# untitled.net
KiCad netlist of a schematic drawn in EAGLE
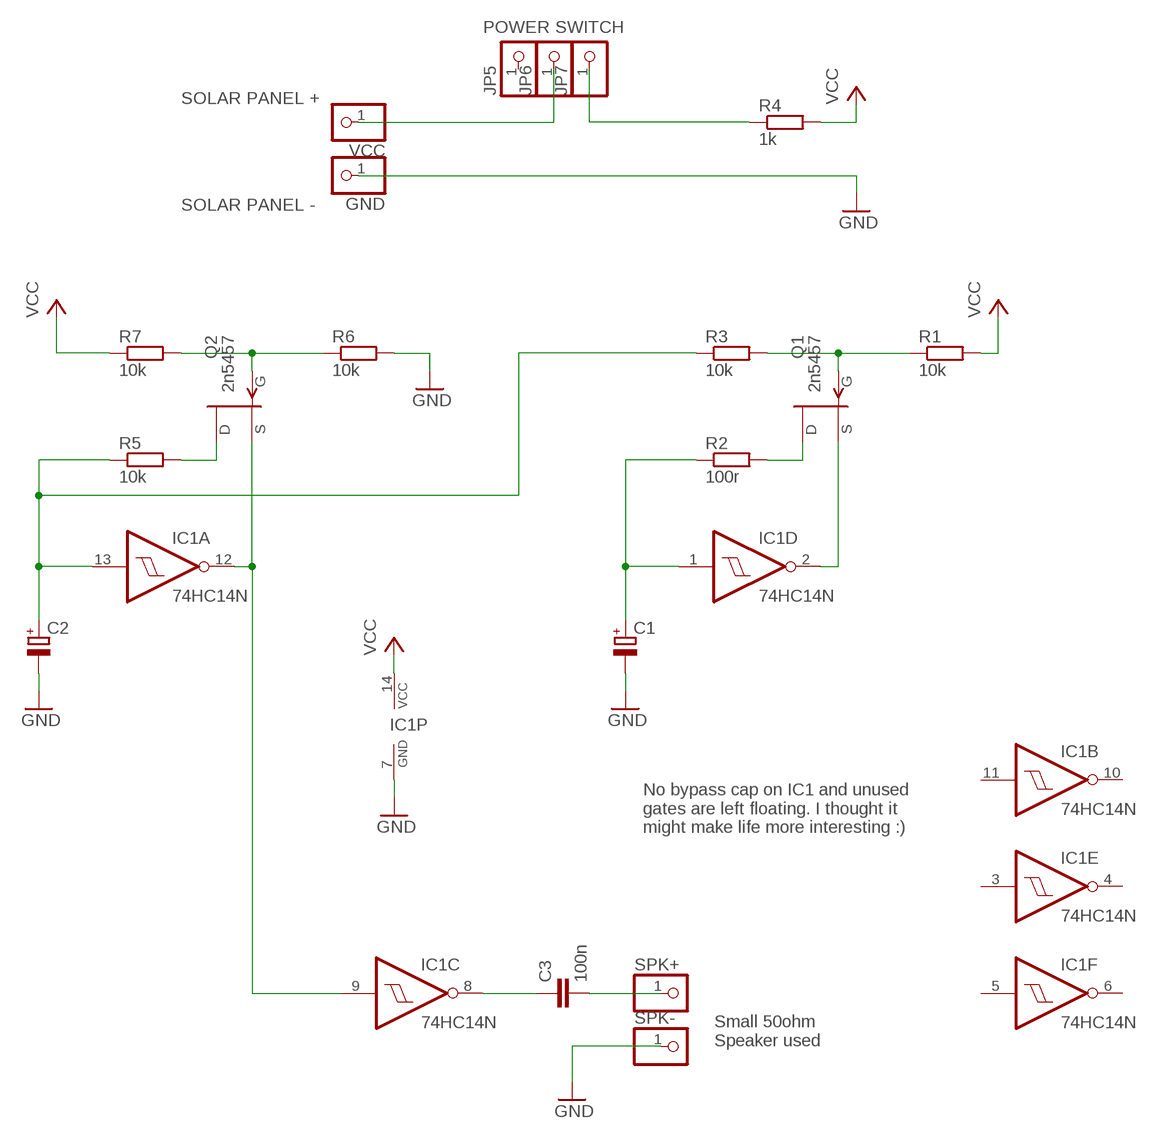
[diagram p0: schematic, sheet 1]

(export (version "E")
  (design (tool "Eeschema 10.0.6"))
  (components
    (comp (ref "C1")
      (value "CPOL-EUE2.5-5")
      (footprint "eagle-import:E2,5-5")
      (libsource (lib "eagle-import") (part "CPOL-EUE2.5-5"))
    )
    (comp (ref "C2")
      (value "CPOL-EUE2.5-5")
      (footprint "eagle-import:E2,5-5")
      (libsource (lib "eagle-import") (part "CPOL-EUE2.5-5"))
    )
    (comp (ref "C3")
      (value "100n")
      (footprint "eagle-import:C025-025X050")
      (libsource (lib "eagle-import") (part "C-EU025-025X050"))
    )
    (comp (ref "GND")
      (value "PINHD-1X1")
      (footprint "eagle-import:1X01")
      (libsource (lib "eagle-import") (part "PINHD-1X1"))
    )
    (comp (ref "IC1")
      (value "74HC14N")
      (footprint "eagle-import:DIL14")
      (libsource (lib "eagle-import") (part "7414NHC"))
    )
    (comp (ref "JP5")
      (value "PINHD-1X1")
      (footprint "eagle-import:1X01")
      (libsource (lib "eagle-import") (part "PINHD-1X1"))
    )
    (comp (ref "JP6")
      (value "PINHD-1X1")
      (footprint "eagle-import:1X01")
      (libsource (lib "eagle-import") (part "PINHD-1X1"))
    )
    (comp (ref "JP7")
      (value "PINHD-1X1")
      (footprint "eagle-import:1X01")
      (libsource (lib "eagle-import") (part "PINHD-1X1"))
    )
    (comp (ref "Q1")
      (value "2n5457")
      (footprint "eagle-import:TO92-")
      (libsource (lib "eagle-import") (part "?5482N4"))
    )
    (comp (ref "Q2")
      (value "2n5457")
      (footprint "eagle-import:TO92-")
      (libsource (lib "eagle-import") (part "?5482N4"))
    )
    (comp (ref "R1")
      (value "10k")
      (footprint "eagle-import:0207_10")
      (libsource (lib "eagle-import") (part "R-EU_0207/10"))
    )
    (comp (ref "R2")
      (value "100r")
      (footprint "eagle-import:0207_10")
      (libsource (lib "eagle-import") (part "R-EU_0207/10"))
    )
    (comp (ref "R3")
      (value "10k")
      (footprint "eagle-import:0207_10")
      (libsource (lib "eagle-import") (part "R-EU_0207/10"))
    )
    (comp (ref "R4")
      (value "1k")
      (footprint "eagle-import:0207_10")
      (libsource (lib "eagle-import") (part "R-EU_0207/10"))
    )
    (comp (ref "R5")
      (value "10k")
      (footprint "eagle-import:0207_10")
      (libsource (lib "eagle-import") (part "R-EU_0207/10"))
    )
    (comp (ref "R6")
      (value "10k")
      (footprint "eagle-import:0207_10")
      (libsource (lib "eagle-import") (part "R-EU_0207/10"))
    )
    (comp (ref "R7")
      (value "10k")
      (footprint "eagle-import:0207_10")
      (libsource (lib "eagle-import") (part "R-EU_0207/10"))
    )
    (comp (ref "SPK+")
      (value "PINHD-1X1")
      (footprint "eagle-import:1X01")
      (libsource (lib "eagle-import") (part "PINHD-1X1"))
    )
    (comp (ref "SPK-")
      (value "PINHD-1X1")
      (footprint "eagle-import:1X01")
      (libsource (lib "eagle-import") (part "PINHD-1X1"))
    )
    (comp (ref "VCC")
      (value "PINHD-1X1")
      (footprint "eagle-import:1X01")
      (libsource (lib "eagle-import") (part "PINHD-1X1"))
    )
  )
  (nets
    (net (code "1") (name "GND") (class "Default")
      (node (ref "C1") (pin "-") (pinfunction "-_-") (pintype "passive"))
      (node (ref "C2") (pin "-") (pinfunction "-_-") (pintype "passive"))
      (node (ref "GND") (pin "1") (pinfunction "1_1") (pintype "passive"))
      (node (ref "IC1") (pin "7") (pinfunction "GND_7") (pintype "power_in"))
      (node (ref "R6") (pin "2") (pinfunction "2_2") (pintype "passive"))
      (node (ref "SPK-") (pin "1") (pinfunction "1_1") (pintype "passive"))
    )
    (net (code "2") (name "Net-(C3-Pad2)") (class "Default")
      (node (ref "C3") (pin "2") (pinfunction "2_2") (pintype "passive"))
      (node (ref "SPK+") (pin "1") (pinfunction "1_1") (pintype "passive"))
    )
    (net (code "3") (name "Net-(IC1A-I)") (class "Default")
      (node (ref "C2") (pin "+") (pinfunction "+_+") (pintype "passive"))
      (node (ref "IC1") (pin "13") (pinfunction "I_13") (pintype "input"))
      (node (ref "R3") (pin "1") (pinfunction "1_1") (pintype "passive"))
      (node (ref "R5") (pin "1") (pinfunction "1_1") (pintype "passive"))
    )
    (net (code "4") (name "Net-(IC1A-O)") (class "Default")
      (node (ref "IC1") (pin "12") (pinfunction "O_12") (pintype "output"))
      (node (ref "IC1") (pin "9") (pinfunction "I_9") (pintype "input"))
      (node (ref "Q2") (pin "2") (pinfunction "S_2") (pintype "passive"))
    )
    (net (code "5") (name "Net-(IC1C-O)") (class "Default")
      (node (ref "C3") (pin "1") (pinfunction "1_1") (pintype "passive"))
      (node (ref "IC1") (pin "8") (pinfunction "O_8") (pintype "output"))
    )
    (net (code "6") (name "Net-(IC1D-I)") (class "Default")
      (node (ref "C1") (pin "+") (pinfunction "+_+") (pintype "passive"))
      (node (ref "IC1") (pin "1") (pinfunction "I_1") (pintype "input"))
      (node (ref "R2") (pin "1") (pinfunction "1_1") (pintype "passive"))
    )
    (net (code "7") (name "Net-(IC1D-O)") (class "Default")
      (node (ref "IC1") (pin "2") (pinfunction "O_2") (pintype "output"))
      (node (ref "Q1") (pin "2") (pinfunction "S_2") (pintype "passive"))
    )
    (net (code "8") (name "Net-(JP6-Pad1)") (class "Default")
      (node (ref "JP6") (pin "1") (pinfunction "1_1") (pintype "passive"))
      (node (ref "VCC") (pin "1") (pinfunction "1_1") (pintype "passive"))
    )
    (net (code "9") (name "Net-(JP7-Pad1)") (class "Default")
      (node (ref "JP7") (pin "1") (pinfunction "1_1") (pintype "passive"))
      (node (ref "R4") (pin "1") (pinfunction "1_1") (pintype "passive"))
    )
    (net (code "10") (name "Net-(Q1-D)") (class "Default")
      (node (ref "Q1") (pin "3") (pinfunction "D_3") (pintype "passive"))
      (node (ref "R2") (pin "2") (pinfunction "2_2") (pintype "passive"))
    )
    (net (code "11") (name "Net-(Q1-G)") (class "Default")
      (node (ref "Q1") (pin "1") (pinfunction "G_1") (pintype "passive"))
      (node (ref "R1") (pin "1") (pinfunction "1_1") (pintype "passive"))
      (node (ref "R3") (pin "2") (pinfunction "2_2") (pintype "passive"))
    )
    (net (code "12") (name "Net-(Q2-D)") (class "Default")
      (node (ref "Q2") (pin "3") (pinfunction "D_3") (pintype "passive"))
      (node (ref "R5") (pin "2") (pinfunction "2_2") (pintype "passive"))
    )
    (net (code "13") (name "Net-(Q2-G)") (class "Default")
      (node (ref "Q2") (pin "1") (pinfunction "G_1") (pintype "passive"))
      (node (ref "R6") (pin "1") (pinfunction "1_1") (pintype "passive"))
      (node (ref "R7") (pin "2") (pinfunction "2_2") (pintype "passive"))
    )
    (net (code "14") (name "VCC") (class "Default")
      (node (ref "IC1") (pin "14") (pinfunction "VCC_14") (pintype "power_in"))
      (node (ref "R1") (pin "2") (pinfunction "2_2") (pintype "passive"))
      (node (ref "R4") (pin "2") (pinfunction "2_2") (pintype "passive"))
      (node (ref "R7") (pin "1") (pinfunction "1_1") (pintype "passive"))
    )
    (net (code "15") (name "unconnected-(IC1B-I-Pad11)") (class "Default")
      (node (ref "IC1") (pin "11") (pinfunction "I_11") (pintype "input"))
    )
    (net (code "16") (name "unconnected-(IC1B-O-Pad10)") (class "Default")
      (node (ref "IC1") (pin "10") (pinfunction "O_10") (pintype "output"))
    )
    (net (code "17") (name "unconnected-(IC1E-I-Pad3)") (class "Default")
      (node (ref "IC1") (pin "3") (pinfunction "I_3") (pintype "input"))
    )
    (net (code "18") (name "unconnected-(IC1E-O-Pad4)") (class "Default")
      (node (ref "IC1") (pin "4") (pinfunction "O_4") (pintype "output"))
    )
    (net (code "19") (name "unconnected-(IC1F-I-Pad5)") (class "Default")
      (node (ref "IC1") (pin "5") (pinfunction "I_5") (pintype "input"))
    )
    (net (code "20") (name "unconnected-(IC1F-O-Pad6)") (class "Default")
      (node (ref "IC1") (pin "6") (pinfunction "O_6") (pintype "output"))
    )
    (net (code "21") (name "unconnected-(JP5-Pad1)") (class "Default")
      (node (ref "JP5") (pin "1") (pinfunction "1_1") (pintype "passive"))
    )
  )
)
